# microSRCPShieldV1.net
KiCad netlist of a schematic drawn in EAGLE
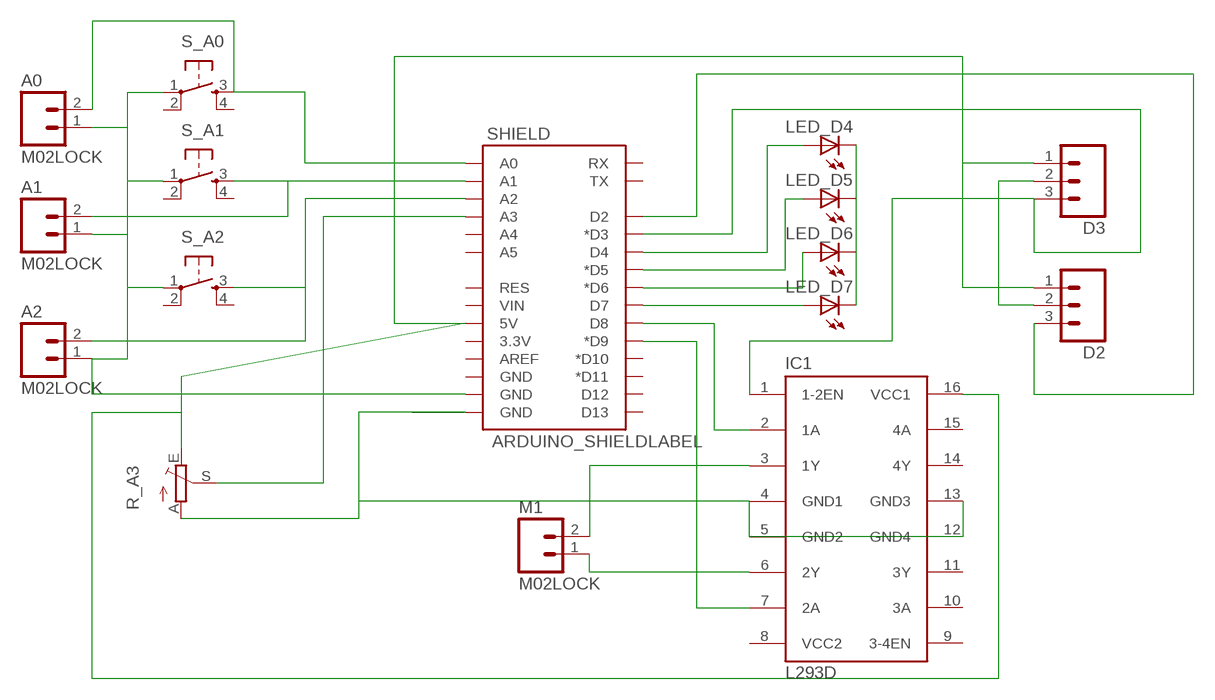
[diagram p0: schematic, sheet 1]

(export (version "E")
  (design (tool "Eeschema 10.0.6"))
  (components
    (comp (ref "A0")
      (value "M02LOCK")
      (footprint "eagle-import:1X02_LOCK")
      (libsource (lib "eagle-import") (part "M02LOCK"))
    )
    (comp (ref "A1")
      (value "M02LOCK")
      (footprint "eagle-import:1X02_LOCK")
      (libsource (lib "eagle-import") (part "M02LOCK"))
    )
    (comp (ref "A2")
      (value "M02LOCK")
      (footprint "eagle-import:1X02_LOCK")
      (libsource (lib "eagle-import") (part "M02LOCK"))
    )
    (comp (ref "D2")
      (value "M03LOCK")
      (footprint "eagle-import:1X03_LOCK")
      (libsource (lib "eagle-import") (part "M03LOCK"))
    )
    (comp (ref "D3")
      (value "M03LOCK")
      (footprint "eagle-import:1X03_LOCK")
      (libsource (lib "eagle-import") (part "M03LOCK"))
    )
    (comp (ref "IC1")
      (value "L293D")
      (footprint "eagle-import:DIL16")
      (libsource (lib "eagle-import") (part "L293D"))
    )
    (comp (ref "LED_D4")
      (value "LED3MM")
      (footprint "eagle-import:LED3MM")
      (libsource (lib "eagle-import") (part "LED3MM"))
    )
    (comp (ref "LED_D5")
      (value "LED3MM")
      (footprint "eagle-import:LED3MM")
      (libsource (lib "eagle-import") (part "LED3MM"))
    )
    (comp (ref "LED_D6")
      (value "LED3MM")
      (footprint "eagle-import:LED3MM")
      (libsource (lib "eagle-import") (part "LED3MM"))
    )
    (comp (ref "LED_D7")
      (value "LED3MM")
      (footprint "eagle-import:LED3MM")
      (libsource (lib "eagle-import") (part "LED3MM"))
    )
    (comp (ref "M1")
      (value "M02LOCK")
      (footprint "eagle-import:1X02_LOCK")
      (libsource (lib "eagle-import") (part "M02LOCK"))
    )
    (comp (ref "R_A3")
      (value "TRIM_EU-PT10S")
      (footprint "eagle-import:PT-10S")
      (libsource (lib "eagle-import") (part "TRIM_EU-PT10S"))
    )
    (comp (ref "SHIELD")
      (value "ARDUINO_SHIELDLABEL")
      (footprint "eagle-import:DUEMILANOVE_SHIELD")
      (libsource (lib "eagle-import") (part "ARDUINO_SHIELDLABEL"))
    )
    (comp (ref "S_A0")
      (value "TAC_SWITCHPTH")
      (footprint "eagle-import:TACTILE-PTH")
      (libsource (lib "eagle-import") (part "TAC_SWITCHPTH"))
    )
    (comp (ref "S_A1")
      (value "TAC_SWITCHPTH")
      (footprint "eagle-import:TACTILE-PTH")
      (libsource (lib "eagle-import") (part "TAC_SWITCHPTH"))
    )
    (comp (ref "S_A2")
      (value "TAC_SWITCHPTH")
      (footprint "eagle-import:TACTILE-PTH")
      (libsource (lib "eagle-import") (part "TAC_SWITCHPTH"))
    )
  )
  (nets
    (net (code "1") (name "/VCC2") (class "Default")
      (node (ref "IC1") (pin "8") (pinfunction "VCC2_8") (pintype "power_in"))
    )
    (net (code "2") (name "Net-(A0-Pad1)") (class "Default")
      (node (ref "A0") (pin "1") (pinfunction "1_1") (pintype "passive"))
      (node (ref "A1") (pin "1") (pinfunction "1_1") (pintype "passive"))
      (node (ref "A2") (pin "1") (pinfunction "1_1") (pintype "passive"))
      (node (ref "SHIELD") (pin "GND@1") (pinfunction "GND_GND@1") (pintype "bidirectional"))
      (node (ref "S_A0") (pin "1") (pinfunction "1_1") (pintype "passive"))
      (node (ref "S_A1") (pin "1") (pinfunction "1_1") (pintype "passive"))
      (node (ref "S_A2") (pin "1") (pinfunction "1_1") (pintype "passive"))
    )
    (net (code "3") (name "Net-(A0-Pad2)") (class "Default")
      (node (ref "A0") (pin "2") (pinfunction "2_2") (pintype "passive"))
      (node (ref "SHIELD") (pin "A0") (pinfunction "A0_A0") (pintype "bidirectional"))
      (node (ref "S_A0") (pin "3") (pinfunction "3_3") (pintype "passive"))
    )
    (net (code "4") (name "Net-(A1-Pad2)") (class "Default")
      (node (ref "A1") (pin "2") (pinfunction "2_2") (pintype "passive"))
      (node (ref "SHIELD") (pin "A1") (pinfunction "A1_A1") (pintype "bidirectional"))
      (node (ref "S_A1") (pin "3") (pinfunction "3_3") (pintype "passive"))
    )
    (net (code "5") (name "Net-(A2-Pad2)") (class "Default")
      (node (ref "A2") (pin "2") (pinfunction "2_2") (pintype "passive"))
      (node (ref "SHIELD") (pin "A2") (pinfunction "A2_A2") (pintype "bidirectional"))
      (node (ref "S_A2") (pin "3") (pinfunction "3_3") (pintype "passive"))
    )
    (net (code "6") (name "Net-(D2-Pad2)") (class "Default")
      (node (ref "D2") (pin "2") (pinfunction "2_2") (pintype "passive"))
      (node (ref "D3") (pin "2") (pinfunction "2_2") (pintype "passive"))
    )
    (net (code "7") (name "Net-(D2-Pad3)") (class "Default")
      (node (ref "D2") (pin "3") (pinfunction "3_3") (pintype "passive"))
      (node (ref "SHIELD") (pin "D2") (pinfunction "D2_D2") (pintype "bidirectional"))
    )
    (net (code "8") (name "Net-(IC1-1-2EN)") (class "Default")
      (node (ref "D3") (pin "3") (pinfunction "3_3") (pintype "passive"))
      (node (ref "IC1") (pin "1") (pinfunction "1-2EN_1") (pintype "input"))
      (node (ref "SHIELD") (pin "D3") (pinfunction "*D3_D3") (pintype "bidirectional"))
    )
    (net (code "9") (name "Net-(IC1-1A)") (class "Default")
      (node (ref "IC1") (pin "2") (pinfunction "1A_2") (pintype "input"))
      (node (ref "SHIELD") (pin "D8") (pinfunction "D8_D8") (pintype "bidirectional"))
    )
    (net (code "10") (name "Net-(IC1-1Y)") (class "Default")
      (node (ref "IC1") (pin "3") (pinfunction "1Y_3") (pintype "output"))
      (node (ref "M1") (pin "2") (pinfunction "2_2") (pintype "passive"))
    )
    (net (code "11") (name "Net-(IC1-2A)") (class "Default")
      (node (ref "IC1") (pin "7") (pinfunction "2A_7") (pintype "input"))
      (node (ref "SHIELD") (pin "D9") (pinfunction "*D9_D9") (pintype "bidirectional"))
    )
    (net (code "12") (name "Net-(IC1-2Y)") (class "Default")
      (node (ref "IC1") (pin "6") (pinfunction "2Y_6") (pintype "output"))
      (node (ref "M1") (pin "1") (pinfunction "1_1") (pintype "passive"))
    )
    (net (code "13") (name "Net-(IC1-GND1)") (class "Default")
      (node (ref "IC1") (pin "12") (pinfunction "GND4_12") (pintype "power_in"))
      (node (ref "IC1") (pin "13") (pinfunction "GND3_13") (pintype "power_in"))
      (node (ref "IC1") (pin "4") (pinfunction "GND1_4") (pintype "power_in"))
      (node (ref "IC1") (pin "5") (pinfunction "GND2_5") (pintype "power_in"))
      (node (ref "R_A3") (pin "A") (pinfunction "A_A") (pintype "passive"))
      (node (ref "SHIELD") (pin "GND@0") (pinfunction "GND_GND@0") (pintype "bidirectional"))
    )
    (net (code "14") (name "Net-(IC1-VCC1)") (class "Default")
      (node (ref "D2") (pin "1") (pinfunction "1_1") (pintype "passive"))
      (node (ref "D3") (pin "1") (pinfunction "1_1") (pintype "passive"))
      (node (ref "IC1") (pin "16") (pinfunction "VCC1_16") (pintype "power_in"))
      (node (ref "R_A3") (pin "E") (pinfunction "E_E") (pintype "passive"))
      (node (ref "SHIELD") (pin "5V") (pinfunction "5V_5V") (pintype "bidirectional"))
    )
    (net (code "15") (name "Net-(LED_D4-C)") (class "Default")
      (node (ref "LED_D4") (pin "K") (pinfunction "C_K") (pintype "passive"))
      (node (ref "LED_D5") (pin "K") (pinfunction "C_K") (pintype "passive"))
      (node (ref "LED_D6") (pin "K") (pinfunction "C_K") (pintype "passive"))
      (node (ref "LED_D7") (pin "K") (pinfunction "C_K") (pintype "passive"))
    )
    (net (code "16") (name "Net-(LED_D4-PadA)") (class "Default")
      (node (ref "LED_D4") (pin "A") (pinfunction "A_A") (pintype "passive"))
      (node (ref "SHIELD") (pin "D4") (pinfunction "D4_D4") (pintype "bidirectional"))
    )
    (net (code "17") (name "Net-(LED_D7-PadA)") (class "Default")
      (node (ref "LED_D7") (pin "A") (pinfunction "A_A") (pintype "passive"))
      (node (ref "SHIELD") (pin "D7") (pinfunction "D7_D7") (pintype "bidirectional"))
    )
    (net (code "18") (name "Net-(R_A3-PadS)") (class "Default")
      (node (ref "R_A3") (pin "S") (pinfunction "S_S") (pintype "passive"))
      (node (ref "SHIELD") (pin "A3") (pinfunction "A3_A3") (pintype "bidirectional"))
    )
    (net (code "19") (name "Net-(SHIELD-*D5)") (class "Default")
      (node (ref "LED_D5") (pin "A") (pinfunction "A_A") (pintype "passive"))
      (node (ref "SHIELD") (pin "D5") (pinfunction "*D5_D5") (pintype "bidirectional"))
    )
    (net (code "20") (name "Net-(SHIELD-*D6)") (class "Default")
      (node (ref "LED_D6") (pin "A") (pinfunction "A_A") (pintype "passive"))
      (node (ref "SHIELD") (pin "D6") (pinfunction "*D6_D6") (pintype "bidirectional"))
    )
    (net (code "21") (name "unconnected-(IC1-3-4EN-Pad9)") (class "Default")
      (node (ref "IC1") (pin "9") (pinfunction "3-4EN_9") (pintype "input"))
    )
    (net (code "22") (name "unconnected-(IC1-3A-Pad10)") (class "Default")
      (node (ref "IC1") (pin "10") (pinfunction "3A_10") (pintype "input"))
    )
    (net (code "23") (name "unconnected-(IC1-3Y-Pad11)") (class "Default")
      (node (ref "IC1") (pin "11") (pinfunction "3Y_11") (pintype "output"))
    )
    (net (code "24") (name "unconnected-(IC1-4A-Pad15)") (class "Default")
      (node (ref "IC1") (pin "15") (pinfunction "4A_15") (pintype "input"))
    )
    (net (code "25") (name "unconnected-(IC1-4Y-Pad14)") (class "Default")
      (node (ref "IC1") (pin "14") (pinfunction "4Y_14") (pintype "output"))
    )
    (net (code "26") (name "unconnected-(SHIELD-*D10-PadD10)") (class "Default")
      (node (ref "SHIELD") (pin "D10") (pinfunction "*D10_D10") (pintype "bidirectional"))
    )
    (net (code "27") (name "unconnected-(SHIELD-*D11-PadD11)") (class "Default")
      (node (ref "SHIELD") (pin "D11") (pinfunction "*D11_D11") (pintype "bidirectional"))
    )
    (net (code "28") (name "unconnected-(SHIELD-GND-PadGND@2)") (class "Default")
      (node (ref "SHIELD") (pin "GND@2") (pinfunction "GND_GND@2") (pintype "bidirectional"))
    )
    (net (code "29") (name "unconnected-(SHIELD-Pad3.3V)") (class "Default")
      (node (ref "SHIELD") (pin "3.3V") (pinfunction "3.3V_3.3V") (pintype "bidirectional"))
    )
    (net (code "30") (name "unconnected-(SHIELD-PadA4)") (class "Default")
      (node (ref "SHIELD") (pin "A4") (pinfunction "A4_A4") (pintype "bidirectional"))
    )
    (net (code "31") (name "unconnected-(SHIELD-PadA5)") (class "Default")
      (node (ref "SHIELD") (pin "A5") (pinfunction "A5_A5") (pintype "bidirectional"))
    )
    (net (code "32") (name "unconnected-(SHIELD-PadAREF)") (class "Default")
      (node (ref "SHIELD") (pin "AREF") (pinfunction "AREF_AREF") (pintype "bidirectional"))
    )
    (net (code "33") (name "unconnected-(SHIELD-PadD12)") (class "Default")
      (node (ref "SHIELD") (pin "D12") (pinfunction "D12_D12") (pintype "bidirectional"))
    )
    (net (code "34") (name "unconnected-(SHIELD-PadD13)") (class "Default")
      (node (ref "SHIELD") (pin "D13") (pinfunction "D13_D13") (pintype "bidirectional"))
    )
    (net (code "35") (name "unconnected-(SHIELD-PadRES)") (class "Default")
      (node (ref "SHIELD") (pin "RES") (pinfunction "RES_RES") (pintype "bidirectional"))
    )
    (net (code "36") (name "unconnected-(SHIELD-PadRX)") (class "Default")
      (node (ref "SHIELD") (pin "RX") (pinfunction "RX_RX") (pintype "bidirectional"))
    )
    (net (code "37") (name "unconnected-(SHIELD-PadTX)") (class "Default")
      (node (ref "SHIELD") (pin "TX") (pinfunction "TX_TX") (pintype "bidirectional"))
    )
    (net (code "38") (name "unconnected-(SHIELD-PadVIN)") (class "Default")
      (node (ref "SHIELD") (pin "VIN") (pinfunction "VIN_VIN") (pintype "bidirectional"))
    )
    (net (code "39") (name "unconnected-(S_A0-Pad2)") (class "Default")
      (node (ref "S_A0") (pin "2") (pinfunction "2_2") (pintype "passive"))
    )
    (net (code "40") (name "unconnected-(S_A0-Pad4)") (class "Default")
      (node (ref "S_A0") (pin "4") (pinfunction "4_4") (pintype "passive"))
    )
    (net (code "41") (name "unconnected-(S_A1-Pad2)") (class "Default")
      (node (ref "S_A1") (pin "2") (pinfunction "2_2") (pintype "passive"))
    )
    (net (code "42") (name "unconnected-(S_A1-Pad4)") (class "Default")
      (node (ref "S_A1") (pin "4") (pinfunction "4_4") (pintype "passive"))
    )
    (net (code "43") (name "unconnected-(S_A2-Pad2)") (class "Default")
      (node (ref "S_A2") (pin "2") (pinfunction "2_2") (pintype "passive"))
    )
    (net (code "44") (name "unconnected-(S_A2-Pad4)") (class "Default")
      (node (ref "S_A2") (pin "4") (pinfunction "4_4") (pintype "passive"))
    )
  )
)
